# Avalon_BP.net
KiCad netlist of a schematic drawn in Altium Designer
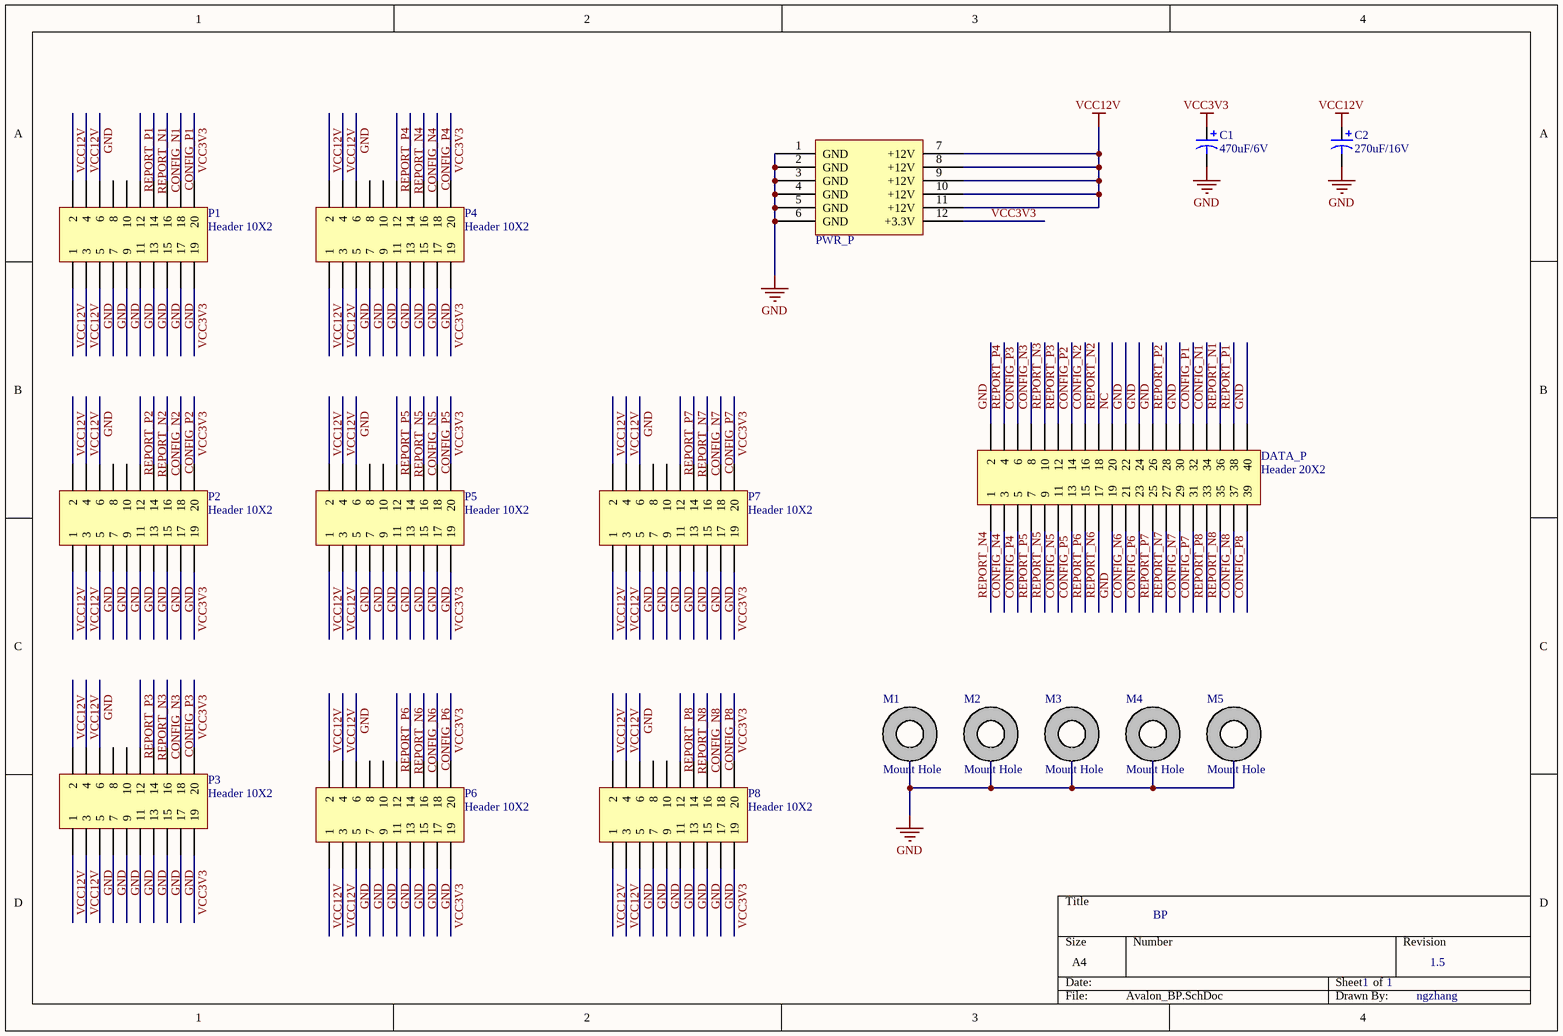
[diagram p0: Avalon_BP.SchDoc]

(export (version "E")
  (design (tool "Eeschema 10.0.6"))
  (components
    (comp (ref "C1")
      (value "470uF/6V")
      (footprint "CAP8X8")
      (description "Polarized Capacitor (Surface Mount)")
      (fields (field (name "PUBLISHER") "Altium Limited"))
      (libsource (lib "S6_2") (part "Cap Pol3"))
    )
    (comp (ref "C2")
      (value "270uF/16V")
      (footprint "CAP8X8")
      (description "Polarized Capacitor (Surface Mount)")
      (fields (field (name "PUBLISHER") "Altium Limited"))
      (libsource (lib "S6_2") (part "Cap Pol3"))
    )
    (comp (ref "DATA_P")
      (value "Header 20X2")
      (footprint "IDE40")
      (description "Header, 20-Pin, Dual row")
      (fields (field (name "PUBLISHER") "Altium Limited"))
      (libsource (lib "Miscellaneous Connectors") (part "Header 20X2"))
    )
    (comp (ref "M1") (value "Mount Hole") (footprint "MHOLE3") (libsource (lib "S6_2") (part "M_Hole")))
    (comp (ref "M2") (value "Mount Hole") (footprint "MHOLE3") (libsource (lib "S6_2") (part "M_Hole")))
    (comp (ref "M3") (value "Mount Hole") (footprint "MHOLE3") (libsource (lib "S6_2") (part "M_Hole")))
    (comp (ref "M4") (value "Mount Hole") (footprint "MHOLE3") (libsource (lib "S6_2") (part "M_Hole")))
    (comp (ref "M5") (value "Mount Hole") (footprint "MHOLE3") (libsource (lib "S6_2") (part "M_Hole")))
    (comp (ref "P1")
      (value "Header 10X2")
      (footprint "HDR2X10")
      (description "Header, 10-Pin, Dual row")
      (fields (field (name "PUBLISHER") "Altium Limited"))
      (libsource (lib "Miscellaneous Connectors") (part "Header 10X2"))
    )
    (comp (ref "P2")
      (value "Header 10X2")
      (footprint "HDR2X10")
      (description "Header, 10-Pin, Dual row")
      (fields (field (name "PUBLISHER") "Altium Limited"))
      (libsource (lib "Miscellaneous Connectors") (part "Header 10X2"))
    )
    (comp (ref "P3")
      (value "Header 10X2")
      (footprint "HDR2X10")
      (description "Header, 10-Pin, Dual row")
      (fields (field (name "PUBLISHER") "Altium Limited"))
      (libsource (lib "Miscellaneous Connectors") (part "Header 10X2"))
    )
    (comp (ref "P4")
      (value "Header 10X2")
      (footprint "HDR2X10")
      (description "Header, 10-Pin, Dual row")
      (fields (field (name "PUBLISHER") "Altium Limited"))
      (libsource (lib "Miscellaneous Connectors") (part "Header 10X2"))
    )
    (comp (ref "P5")
      (value "Header 10X2")
      (footprint "HDR2X10")
      (description "Header, 10-Pin, Dual row")
      (fields (field (name "PUBLISHER") "Altium Limited"))
      (libsource (lib "Miscellaneous Connectors") (part "Header 10X2"))
    )
    (comp (ref "P6")
      (value "Header 10X2")
      (footprint "HDR2X10")
      (description "Header, 10-Pin, Dual row")
      (fields (field (name "PUBLISHER") "Altium Limited"))
      (libsource (lib "Miscellaneous Connectors") (part "Header 10X2"))
    )
    (comp (ref "P7")
      (value "Header 10X2")
      (footprint "HDR2X10")
      (description "Header, 10-Pin, Dual row")
      (fields (field (name "PUBLISHER") "Altium Limited"))
      (libsource (lib "Miscellaneous Connectors") (part "Header 10X2"))
    )
    (comp (ref "P8")
      (value "Header 10X2")
      (footprint "HDR2X10")
      (description "Header, 10-Pin, Dual row")
      (fields (field (name "PUBLISHER") "Altium Limited"))
      (libsource (lib "Miscellaneous Connectors") (part "Header 10X2"))
    )
    (comp (ref "PWR_P")
      (value "PWR_12P")
      (footprint "PWR_12PIN")
      (libsource (lib "power_adapter") (part "PWR_12P"))
    )
  )
  (nets
    (net (code "1") (name "/CONFIG_N1") (class "Default")
      (node (ref "DATA_P") (pin "34") (pinfunction "34_34") (pintype "passive"))
      (node (ref "P1") (pin "16") (pinfunction "16_16") (pintype "passive"))
    )
    (net (code "2") (name "/CONFIG_N2") (class "Default")
      (node (ref "DATA_P") (pin "16") (pinfunction "16_16") (pintype "passive"))
      (node (ref "P2") (pin "16") (pinfunction "16_16") (pintype "passive"))
    )
    (net (code "3") (name "/CONFIG_N3") (class "Default")
      (node (ref "DATA_P") (pin "8") (pinfunction "8_8") (pintype "passive"))
      (node (ref "P3") (pin "16") (pinfunction "16_16") (pintype "passive"))
    )
    (net (code "4") (name "/CONFIG_N4") (class "Default")
      (node (ref "DATA_P") (pin "3") (pinfunction "3_3") (pintype "passive"))
      (node (ref "P4") (pin "16") (pinfunction "16_16") (pintype "passive"))
    )
    (net (code "5") (name "/CONFIG_N5") (class "Default")
      (node (ref "DATA_P") (pin "11") (pinfunction "11_11") (pintype "passive"))
      (node (ref "P5") (pin "16") (pinfunction "16_16") (pintype "passive"))
    )
    (net (code "6") (name "/CONFIG_N6") (class "Default")
      (node (ref "DATA_P") (pin "21") (pinfunction "21_21") (pintype "passive"))
      (node (ref "P6") (pin "16") (pinfunction "16_16") (pintype "passive"))
    )
    (net (code "7") (name "/CONFIG_N7") (class "Default")
      (node (ref "DATA_P") (pin "29") (pinfunction "29_29") (pintype "passive"))
      (node (ref "P7") (pin "16") (pinfunction "16_16") (pintype "passive"))
    )
    (net (code "8") (name "/CONFIG_N8") (class "Default")
      (node (ref "DATA_P") (pin "37") (pinfunction "37_37") (pintype "passive"))
      (node (ref "P8") (pin "16") (pinfunction "16_16") (pintype "passive"))
    )
    (net (code "9") (name "/CONFIG_P1") (class "Default")
      (node (ref "DATA_P") (pin "32") (pinfunction "32_32") (pintype "passive"))
      (node (ref "P1") (pin "18") (pinfunction "18_18") (pintype "passive"))
    )
    (net (code "10") (name "/CONFIG_P2") (class "Default")
      (node (ref "DATA_P") (pin "14") (pinfunction "14_14") (pintype "passive"))
      (node (ref "P2") (pin "18") (pinfunction "18_18") (pintype "passive"))
    )
    (net (code "11") (name "/CONFIG_P3") (class "Default")
      (node (ref "DATA_P") (pin "6") (pinfunction "6_6") (pintype "passive"))
      (node (ref "P3") (pin "18") (pinfunction "18_18") (pintype "passive"))
    )
    (net (code "12") (name "/CONFIG_P4") (class "Default")
      (node (ref "DATA_P") (pin "5") (pinfunction "5_5") (pintype "passive"))
      (node (ref "P4") (pin "18") (pinfunction "18_18") (pintype "passive"))
    )
    (net (code "13") (name "/CONFIG_P5") (class "Default")
      (node (ref "DATA_P") (pin "13") (pinfunction "13_13") (pintype "passive"))
      (node (ref "P5") (pin "18") (pinfunction "18_18") (pintype "passive"))
    )
    (net (code "14") (name "/CONFIG_P6") (class "Default")
      (node (ref "DATA_P") (pin "23") (pinfunction "23_23") (pintype "passive"))
      (node (ref "P6") (pin "18") (pinfunction "18_18") (pintype "passive"))
    )
    (net (code "15") (name "/CONFIG_P7") (class "Default")
      (node (ref "DATA_P") (pin "31") (pinfunction "31_31") (pintype "passive"))
      (node (ref "P7") (pin "18") (pinfunction "18_18") (pintype "passive"))
    )
    (net (code "16") (name "/CONFIG_P8") (class "Default")
      (node (ref "DATA_P") (pin "39") (pinfunction "39_39") (pintype "passive"))
      (node (ref "P8") (pin "18") (pinfunction "18_18") (pintype "passive"))
    )
    (net (code "17") (name "/NC") (class "Default")
      (node (ref "DATA_P") (pin "20") (pinfunction "20_20") (pintype "passive"))
    )
    (net (code "18") (name "/REPORT_N1") (class "Default")
      (node (ref "DATA_P") (pin "36") (pinfunction "36_36") (pintype "passive"))
      (node (ref "P1") (pin "14") (pinfunction "14_14") (pintype "passive"))
    )
    (net (code "19") (name "/REPORT_N2") (class "Default")
      (node (ref "DATA_P") (pin "18") (pinfunction "18_18") (pintype "passive"))
      (node (ref "P2") (pin "14") (pinfunction "14_14") (pintype "passive"))
    )
    (net (code "20") (name "/REPORT_N3") (class "Default")
      (node (ref "DATA_P") (pin "10") (pinfunction "10_10") (pintype "passive"))
      (node (ref "P3") (pin "14") (pinfunction "14_14") (pintype "passive"))
    )
    (net (code "21") (name "/REPORT_N4") (class "Default")
      (node (ref "DATA_P") (pin "1") (pinfunction "1_1") (pintype "passive"))
      (node (ref "P4") (pin "14") (pinfunction "14_14") (pintype "passive"))
    )
    (net (code "22") (name "/REPORT_N5") (class "Default")
      (node (ref "DATA_P") (pin "9") (pinfunction "9_9") (pintype "passive"))
      (node (ref "P5") (pin "14") (pinfunction "14_14") (pintype "passive"))
    )
    (net (code "23") (name "/REPORT_N6") (class "Default")
      (node (ref "DATA_P") (pin "17") (pinfunction "17_17") (pintype "passive"))
      (node (ref "P6") (pin "14") (pinfunction "14_14") (pintype "passive"))
    )
    (net (code "24") (name "/REPORT_N7") (class "Default")
      (node (ref "DATA_P") (pin "27") (pinfunction "27_27") (pintype "passive"))
      (node (ref "P7") (pin "14") (pinfunction "14_14") (pintype "passive"))
    )
    (net (code "25") (name "/REPORT_N8") (class "Default")
      (node (ref "DATA_P") (pin "35") (pinfunction "35_35") (pintype "passive"))
      (node (ref "P8") (pin "14") (pinfunction "14_14") (pintype "passive"))
    )
    (net (code "26") (name "/REPORT_P1") (class "Default")
      (node (ref "DATA_P") (pin "38") (pinfunction "38_38") (pintype "passive"))
      (node (ref "P1") (pin "12") (pinfunction "12_12") (pintype "passive"))
    )
    (net (code "27") (name "/REPORT_P2") (class "Default")
      (node (ref "DATA_P") (pin "28") (pinfunction "28_28") (pintype "passive"))
      (node (ref "P2") (pin "12") (pinfunction "12_12") (pintype "passive"))
    )
    (net (code "28") (name "/REPORT_P3") (class "Default")
      (node (ref "DATA_P") (pin "12") (pinfunction "12_12") (pintype "passive"))
      (node (ref "P3") (pin "12") (pinfunction "12_12") (pintype "passive"))
    )
    (net (code "29") (name "/REPORT_P4") (class "Default")
      (node (ref "DATA_P") (pin "4") (pinfunction "4_4") (pintype "passive"))
      (node (ref "P4") (pin "12") (pinfunction "12_12") (pintype "passive"))
    )
    (net (code "30") (name "/REPORT_P5") (class "Default")
      (node (ref "DATA_P") (pin "7") (pinfunction "7_7") (pintype "passive"))
      (node (ref "P5") (pin "12") (pinfunction "12_12") (pintype "passive"))
    )
    (net (code "31") (name "/REPORT_P6") (class "Default")
      (node (ref "DATA_P") (pin "15") (pinfunction "15_15") (pintype "passive"))
      (node (ref "P6") (pin "12") (pinfunction "12_12") (pintype "passive"))
    )
    (net (code "32") (name "/REPORT_P7") (class "Default")
      (node (ref "DATA_P") (pin "25") (pinfunction "25_25") (pintype "passive"))
      (node (ref "P7") (pin "12") (pinfunction "12_12") (pintype "passive"))
    )
    (net (code "33") (name "/REPORT_P8") (class "Default")
      (node (ref "DATA_P") (pin "33") (pinfunction "33_33") (pintype "passive"))
      (node (ref "P8") (pin "12") (pinfunction "12_12") (pintype "passive"))
    )
    (net (code "34") (name "GND") (class "Default")
      (node (ref "C1") (pin "2") (pinfunction "2_2") (pintype "passive"))
      (node (ref "C2") (pin "2") (pinfunction "2_2") (pintype "passive"))
      (node (ref "DATA_P") (pin "19") (pinfunction "19_19") (pintype "passive"))
      (node (ref "DATA_P") (pin "2") (pinfunction "2_2") (pintype "passive"))
      (node (ref "DATA_P") (pin "22") (pinfunction "22_22") (pintype "passive"))
      (node (ref "DATA_P") (pin "24") (pinfunction "24_24") (pintype "passive"))
      (node (ref "DATA_P") (pin "26") (pinfunction "26_26") (pintype "passive"))
      (node (ref "DATA_P") (pin "30") (pinfunction "30_30") (pintype "passive"))
      (node (ref "DATA_P") (pin "40") (pinfunction "40_40") (pintype "passive"))
      (node (ref "M1") (pin "0") (pinfunction "PIN_0") (pintype "power_in"))
      (node (ref "M2") (pin "0") (pinfunction "PIN_0") (pintype "power_in"))
      (node (ref "M3") (pin "0") (pinfunction "PIN_0") (pintype "power_in"))
      (node (ref "M4") (pin "0") (pinfunction "PIN_0") (pintype "power_in"))
      (node (ref "M5") (pin "0") (pinfunction "PIN_0") (pintype "power_in"))
      (node (ref "P1") (pin "11") (pinfunction "11_11") (pintype "passive"))
      (node (ref "P1") (pin "13") (pinfunction "13_13") (pintype "passive"))
      (node (ref "P1") (pin "15") (pinfunction "15_15") (pintype "passive"))
      (node (ref "P1") (pin "17") (pinfunction "17_17") (pintype "passive"))
      (node (ref "P1") (pin "5") (pinfunction "5_5") (pintype "passive"))
      (node (ref "P1") (pin "6") (pinfunction "6_6") (pintype "passive"))
      (node (ref "P1") (pin "7") (pinfunction "7_7") (pintype "passive"))
      (node (ref "P1") (pin "9") (pinfunction "9_9") (pintype "passive"))
      (node (ref "P2") (pin "11") (pinfunction "11_11") (pintype "passive"))
      (node (ref "P2") (pin "13") (pinfunction "13_13") (pintype "passive"))
      (node (ref "P2") (pin "15") (pinfunction "15_15") (pintype "passive"))
      (node (ref "P2") (pin "17") (pinfunction "17_17") (pintype "passive"))
      (node (ref "P2") (pin "5") (pinfunction "5_5") (pintype "passive"))
      (node (ref "P2") (pin "6") (pinfunction "6_6") (pintype "passive"))
      (node (ref "P2") (pin "7") (pinfunction "7_7") (pintype "passive"))
      (node (ref "P2") (pin "9") (pinfunction "9_9") (pintype "passive"))
      (node (ref "P3") (pin "11") (pinfunction "11_11") (pintype "passive"))
      (node (ref "P3") (pin "13") (pinfunction "13_13") (pintype "passive"))
      (node (ref "P3") (pin "15") (pinfunction "15_15") (pintype "passive"))
      (node (ref "P3") (pin "17") (pinfunction "17_17") (pintype "passive"))
      (node (ref "P3") (pin "5") (pinfunction "5_5") (pintype "passive"))
      (node (ref "P3") (pin "6") (pinfunction "6_6") (pintype "passive"))
      (node (ref "P3") (pin "7") (pinfunction "7_7") (pintype "passive"))
      (node (ref "P3") (pin "9") (pinfunction "9_9") (pintype "passive"))
      (node (ref "P4") (pin "11") (pinfunction "11_11") (pintype "passive"))
      (node (ref "P4") (pin "13") (pinfunction "13_13") (pintype "passive"))
      (node (ref "P4") (pin "15") (pinfunction "15_15") (pintype "passive"))
      (node (ref "P4") (pin "17") (pinfunction "17_17") (pintype "passive"))
      (node (ref "P4") (pin "5") (pinfunction "5_5") (pintype "passive"))
      (node (ref "P4") (pin "6") (pinfunction "6_6") (pintype "passive"))
      (node (ref "P4") (pin "7") (pinfunction "7_7") (pintype "passive"))
      (node (ref "P4") (pin "9") (pinfunction "9_9") (pintype "passive"))
      (node (ref "P5") (pin "11") (pinfunction "11_11") (pintype "passive"))
      (node (ref "P5") (pin "13") (pinfunction "13_13") (pintype "passive"))
      (node (ref "P5") (pin "15") (pinfunction "15_15") (pintype "passive"))
      (node (ref "P5") (pin "17") (pinfunction "17_17") (pintype "passive"))
      (node (ref "P5") (pin "5") (pinfunction "5_5") (pintype "passive"))
      (node (ref "P5") (pin "6") (pinfunction "6_6") (pintype "passive"))
      (node (ref "P5") (pin "7") (pinfunction "7_7") (pintype "passive"))
      (node (ref "P5") (pin "9") (pinfunction "9_9") (pintype "passive"))
      (node (ref "P6") (pin "11") (pinfunction "11_11") (pintype "passive"))
      (node (ref "P6") (pin "13") (pinfunction "13_13") (pintype "passive"))
      (node (ref "P6") (pin "15") (pinfunction "15_15") (pintype "passive"))
      (node (ref "P6") (pin "17") (pinfunction "17_17") (pintype "passive"))
      (node (ref "P6") (pin "5") (pinfunction "5_5") (pintype "passive"))
      (node (ref "P6") (pin "6") (pinfunction "6_6") (pintype "passive"))
      (node (ref "P6") (pin "7") (pinfunction "7_7") (pintype "passive"))
      (node (ref "P6") (pin "9") (pinfunction "9_9") (pintype "passive"))
      (node (ref "P7") (pin "11") (pinfunction "11_11") (pintype "passive"))
      (node (ref "P7") (pin "13") (pinfunction "13_13") (pintype "passive"))
      (node (ref "P7") (pin "15") (pinfunction "15_15") (pintype "passive"))
      (node (ref "P7") (pin "17") (pinfunction "17_17") (pintype "passive"))
      (node (ref "P7") (pin "5") (pinfunction "5_5") (pintype "passive"))
      (node (ref "P7") (pin "6") (pinfunction "6_6") (pintype "passive"))
      (node (ref "P7") (pin "7") (pinfunction "7_7") (pintype "passive"))
      (node (ref "P7") (pin "9") (pinfunction "9_9") (pintype "passive"))
      (node (ref "P8") (pin "11") (pinfunction "11_11") (pintype "passive"))
      (node (ref "P8") (pin "13") (pinfunction "13_13") (pintype "passive"))
      (node (ref "P8") (pin "15") (pinfunction "15_15") (pintype "passive"))
      (node (ref "P8") (pin "17") (pinfunction "17_17") (pintype "passive"))
      (node (ref "P8") (pin "5") (pinfunction "5_5") (pintype "passive"))
      (node (ref "P8") (pin "6") (pinfunction "6_6") (pintype "passive"))
      (node (ref "P8") (pin "7") (pinfunction "7_7") (pintype "passive"))
      (node (ref "P8") (pin "9") (pinfunction "9_9") (pintype "passive"))
      (node (ref "PWR_P") (pin "1") (pinfunction "GND_1") (pintype "passive"))
      (node (ref "PWR_P") (pin "2") (pinfunction "GND_2") (pintype "passive"))
      (node (ref "PWR_P") (pin "3") (pinfunction "GND_3") (pintype "passive"))
      (node (ref "PWR_P") (pin "4") (pinfunction "GND_4") (pintype "passive"))
      (node (ref "PWR_P") (pin "5") (pinfunction "GND_5") (pintype "passive"))
      (node (ref "PWR_P") (pin "6") (pinfunction "GND_6") (pintype "passive"))
    )
    (net (code "35") (name "VCC3V3") (class "Default")
      (node (ref "C1") (pin "1") (pinfunction "1_1") (pintype "passive"))
      (node (ref "P1") (pin "19") (pinfunction "19_19") (pintype "passive"))
      (node (ref "P1") (pin "20") (pinfunction "20_20") (pintype "passive"))
      (node (ref "P2") (pin "19") (pinfunction "19_19") (pintype "passive"))
      (node (ref "P2") (pin "20") (pinfunction "20_20") (pintype "passive"))
      (node (ref "P3") (pin "19") (pinfunction "19_19") (pintype "passive"))
      (node (ref "P3") (pin "20") (pinfunction "20_20") (pintype "passive"))
      (node (ref "P4") (pin "19") (pinfunction "19_19") (pintype "passive"))
      (node (ref "P4") (pin "20") (pinfunction "20_20") (pintype "passive"))
      (node (ref "P5") (pin "19") (pinfunction "19_19") (pintype "passive"))
      (node (ref "P5") (pin "20") (pinfunction "20_20") (pintype "passive"))
      (node (ref "P6") (pin "19") (pinfunction "19_19") (pintype "passive"))
      (node (ref "P6") (pin "20") (pinfunction "20_20") (pintype "passive"))
      (node (ref "P7") (pin "19") (pinfunction "19_19") (pintype "passive"))
      (node (ref "P7") (pin "20") (pinfunction "20_20") (pintype "passive"))
      (node (ref "P8") (pin "19") (pinfunction "19_19") (pintype "passive"))
      (node (ref "P8") (pin "20") (pinfunction "20_20") (pintype "passive"))
      (node (ref "PWR_P") (pin "12") (pinfunction "+3.3V_12") (pintype "passive"))
    )
    (net (code "36") (name "VCC12V") (class "Default")
      (node (ref "C2") (pin "1") (pinfunction "1_1") (pintype "passive"))
      (node (ref "P1") (pin "1") (pinfunction "1_1") (pintype "passive"))
      (node (ref "P1") (pin "2") (pinfunction "2_2") (pintype "passive"))
      (node (ref "P1") (pin "3") (pinfunction "3_3") (pintype "passive"))
      (node (ref "P1") (pin "4") (pinfunction "4_4") (pintype "passive"))
      (node (ref "P2") (pin "1") (pinfunction "1_1") (pintype "passive"))
      (node (ref "P2") (pin "2") (pinfunction "2_2") (pintype "passive"))
      (node (ref "P2") (pin "3") (pinfunction "3_3") (pintype "passive"))
      (node (ref "P2") (pin "4") (pinfunction "4_4") (pintype "passive"))
      (node (ref "P3") (pin "1") (pinfunction "1_1") (pintype "passive"))
      (node (ref "P3") (pin "2") (pinfunction "2_2") (pintype "passive"))
      (node (ref "P3") (pin "3") (pinfunction "3_3") (pintype "passive"))
      (node (ref "P3") (pin "4") (pinfunction "4_4") (pintype "passive"))
      (node (ref "P4") (pin "1") (pinfunction "1_1") (pintype "passive"))
      (node (ref "P4") (pin "2") (pinfunction "2_2") (pintype "passive"))
      (node (ref "P4") (pin "3") (pinfunction "3_3") (pintype "passive"))
      (node (ref "P4") (pin "4") (pinfunction "4_4") (pintype "passive"))
      (node (ref "P5") (pin "1") (pinfunction "1_1") (pintype "passive"))
      (node (ref "P5") (pin "2") (pinfunction "2_2") (pintype "passive"))
      (node (ref "P5") (pin "3") (pinfunction "3_3") (pintype "passive"))
      (node (ref "P5") (pin "4") (pinfunction "4_4") (pintype "passive"))
      (node (ref "P6") (pin "1") (pinfunction "1_1") (pintype "passive"))
      (node (ref "P6") (pin "2") (pinfunction "2_2") (pintype "passive"))
      (node (ref "P6") (pin "3") (pinfunction "3_3") (pintype "passive"))
      (node (ref "P6") (pin "4") (pinfunction "4_4") (pintype "passive"))
      (node (ref "P7") (pin "1") (pinfunction "1_1") (pintype "passive"))
      (node (ref "P7") (pin "2") (pinfunction "2_2") (pintype "passive"))
      (node (ref "P7") (pin "3") (pinfunction "3_3") (pintype "passive"))
      (node (ref "P7") (pin "4") (pinfunction "4_4") (pintype "passive"))
      (node (ref "P8") (pin "1") (pinfunction "1_1") (pintype "passive"))
      (node (ref "P8") (pin "2") (pinfunction "2_2") (pintype "passive"))
      (node (ref "P8") (pin "3") (pinfunction "3_3") (pintype "passive"))
      (node (ref "P8") (pin "4") (pinfunction "4_4") (pintype "passive"))
      (node (ref "PWR_P") (pin "10") (pinfunction "+12V_10") (pintype "passive"))
      (node (ref "PWR_P") (pin "11") (pinfunction "+12V_11") (pintype "passive"))
      (node (ref "PWR_P") (pin "7") (pinfunction "+12V_7") (pintype "passive"))
      (node (ref "PWR_P") (pin "8") (pinfunction "+12V_8") (pintype "passive"))
      (node (ref "PWR_P") (pin "9") (pinfunction "+12V_9") (pintype "passive"))
    )
    (net (code "37") (name "unconnected-(P1-Pad8)") (class "Default")
      (node (ref "P1") (pin "8") (pinfunction "8_8") (pintype "passive"))
    )
    (net (code "38") (name "unconnected-(P1-Pad10)") (class "Default")
      (node (ref "P1") (pin "10") (pinfunction "10_10") (pintype "passive"))
    )
    (net (code "39") (name "unconnected-(P2-Pad8)") (class "Default")
      (node (ref "P2") (pin "8") (pinfunction "8_8") (pintype "passive"))
    )
    (net (code "40") (name "unconnected-(P2-Pad10)") (class "Default")
      (node (ref "P2") (pin "10") (pinfunction "10_10") (pintype "passive"))
    )
    (net (code "41") (name "unconnected-(P3-Pad8)") (class "Default")
      (node (ref "P3") (pin "8") (pinfunction "8_8") (pintype "passive"))
    )
    (net (code "42") (name "unconnected-(P3-Pad10)") (class "Default")
      (node (ref "P3") (pin "10") (pinfunction "10_10") (pintype "passive"))
    )
    (net (code "43") (name "unconnected-(P4-Pad8)") (class "Default")
      (node (ref "P4") (pin "8") (pinfunction "8_8") (pintype "passive"))
    )
    (net (code "44") (name "unconnected-(P4-Pad10)") (class "Default")
      (node (ref "P4") (pin "10") (pinfunction "10_10") (pintype "passive"))
    )
    (net (code "45") (name "unconnected-(P5-Pad8)") (class "Default")
      (node (ref "P5") (pin "8") (pinfunction "8_8") (pintype "passive"))
    )
    (net (code "46") (name "unconnected-(P5-Pad10)") (class "Default")
      (node (ref "P5") (pin "10") (pinfunction "10_10") (pintype "passive"))
    )
    (net (code "47") (name "unconnected-(P6-Pad8)") (class "Default")
      (node (ref "P6") (pin "8") (pinfunction "8_8") (pintype "passive"))
    )
    (net (code "48") (name "unconnected-(P6-Pad10)") (class "Default")
      (node (ref "P6") (pin "10") (pinfunction "10_10") (pintype "passive"))
    )
    (net (code "49") (name "unconnected-(P7-Pad8)") (class "Default")
      (node (ref "P7") (pin "8") (pinfunction "8_8") (pintype "passive"))
    )
    (net (code "50") (name "unconnected-(P7-Pad10)") (class "Default")
      (node (ref "P7") (pin "10") (pinfunction "10_10") (pintype "passive"))
    )
    (net (code "51") (name "unconnected-(P8-Pad8)") (class "Default")
      (node (ref "P8") (pin "8") (pinfunction "8_8") (pintype "passive"))
    )
    (net (code "52") (name "unconnected-(P8-Pad10)") (class "Default")
      (node (ref "P8") (pin "10") (pinfunction "10_10") (pintype "passive"))
    )
  )
)
